# blinking_circuit_training.net
KiCad netlist of a schematic drawn in EAGLE
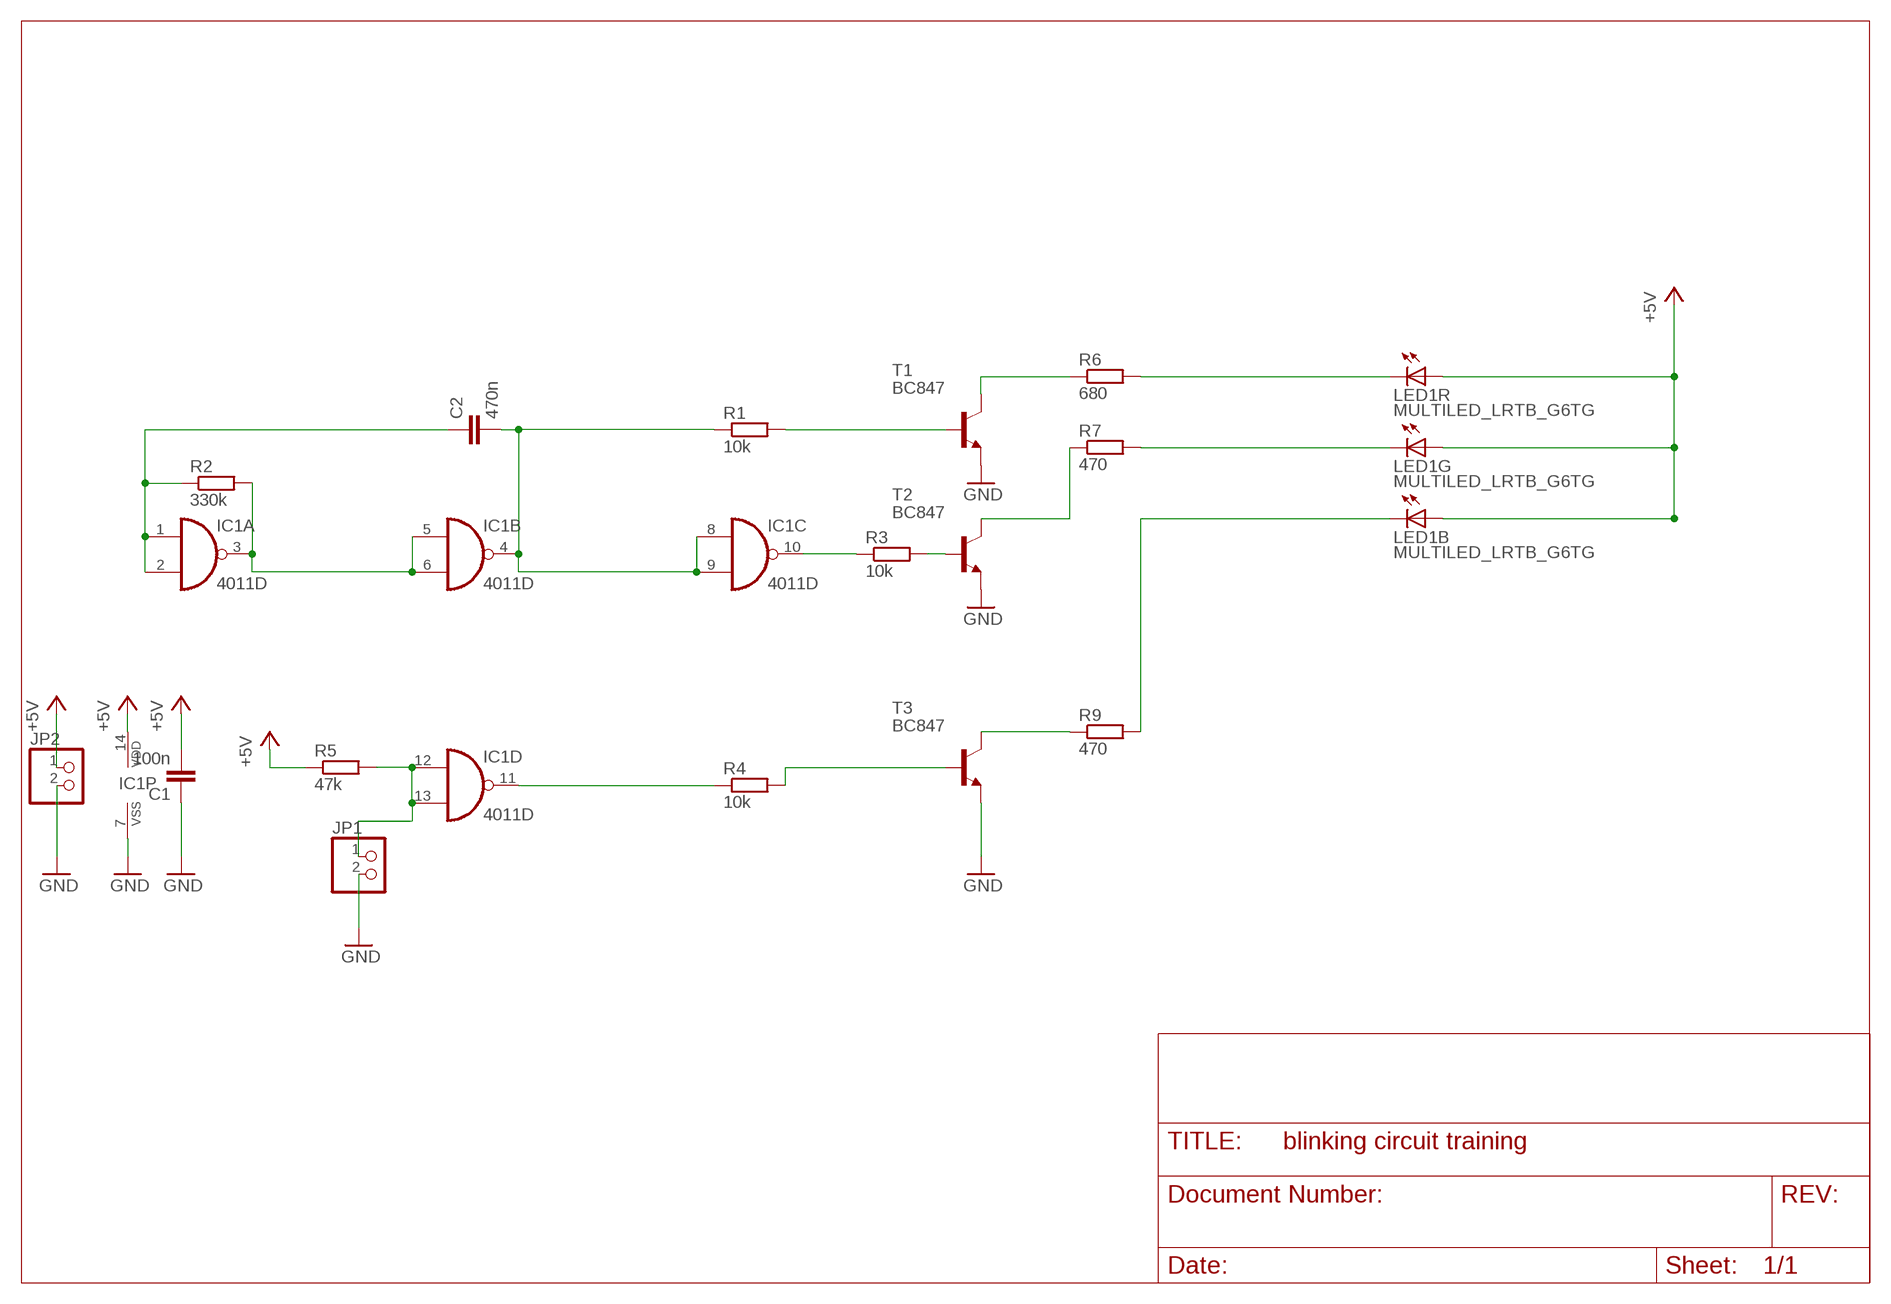
[diagram p0: schematic, sheet 1]

(export (version "E")
  (design (tool "Eeschema 10.0.6"))
  (components
    (comp (ref "C1")
      (value "100n")
      (footprint "eagle-import:C0603")
      (libsource (lib "eagle-import") (part "C-EUC0603"))
    )
    (comp (ref "C2")
      (value "470n")
      (footprint "eagle-import:C0603")
      (libsource (lib "eagle-import") (part "C-EUC0603"))
    )
    (comp (ref "IC1")
      (value "4011D")
      (footprint "eagle-import:SO14")
      (libsource (lib "eagle-import") (part "4011D"))
    )
    (comp (ref "JP1")
      (value "PINHD-1X2")
      (footprint "eagle-import:1X02")
      (libsource (lib "eagle-import") (part "PINHD-1X2"))
    )
    (comp (ref "JP2")
      (value "PINHD-1X2")
      (footprint "eagle-import:1X02")
      (libsource (lib "eagle-import") (part "PINHD-1X2"))
    )
    (comp (ref "LED1")
      (value "MULTILED_LRTB_G6TG")
      (footprint "eagle-import:P-LCC-6_TOPLED")
      (libsource (lib "eagle-import") (part "MULTILED_LRTB_G6TG"))
    )
    (comp (ref "R1")
      (value "10k")
      (footprint "eagle-import:M1206")
      (libsource (lib "eagle-import") (part "R-EU_M1206"))
    )
    (comp (ref "R2")
      (value "330k")
      (footprint "eagle-import:M1206")
      (libsource (lib "eagle-import") (part "R-EU_M1206"))
    )
    (comp (ref "R3")
      (value "10k")
      (footprint "eagle-import:M1206")
      (libsource (lib "eagle-import") (part "R-EU_M1206"))
    )
    (comp (ref "R4")
      (value "10k")
      (footprint "eagle-import:M1206")
      (libsource (lib "eagle-import") (part "R-EU_M1206"))
    )
    (comp (ref "R5")
      (value "47k")
      (footprint "eagle-import:M1206")
      (libsource (lib "eagle-import") (part "R-EU_M1206"))
    )
    (comp (ref "R6")
      (value "680")
      (footprint "eagle-import:M1206")
      (libsource (lib "eagle-import") (part "R-EU_M1206"))
    )
    (comp (ref "R7")
      (value "470")
      (footprint "eagle-import:M1206")
      (libsource (lib "eagle-import") (part "R-EU_M1206"))
    )
    (comp (ref "R9")
      (value "470")
      (footprint "eagle-import:M1206")
      (libsource (lib "eagle-import") (part "R-EU_M1206"))
    )
    (comp (ref "T1")
      (value "BC847")
      (footprint "eagle-import:SOT23")
      (libsource (lib "eagle-import") (part "BC847"))
    )
    (comp (ref "T2")
      (value "BC847")
      (footprint "eagle-import:SOT23")
      (libsource (lib "eagle-import") (part "BC847"))
    )
    (comp (ref "T3")
      (value "BC847")
      (footprint "eagle-import:SOT23")
      (libsource (lib "eagle-import") (part "BC847"))
    )
  )
  (nets
    (net (code "1") (name "+5V") (class "Default")
      (node (ref "C1") (pin "2") (pinfunction "2_2") (pintype "passive"))
      (node (ref "IC1") (pin "14") (pinfunction "VDD_14") (pintype "power_in"))
      (node (ref "JP2") (pin "1") (pinfunction "1_1") (pintype "passive"))
      (node (ref "LED1") (pin "A1") (pinfunction "A_A1") (pintype "passive"))
      (node (ref "LED1") (pin "A2") (pinfunction "A_A2") (pintype "passive"))
      (node (ref "LED1") (pin "A3") (pinfunction "A_A3") (pintype "passive"))
      (node (ref "R5") (pin "1") (pinfunction "1_1") (pintype "passive"))
    )
    (net (code "2") (name "GND") (class "Default")
      (node (ref "C1") (pin "1") (pinfunction "1_1") (pintype "passive"))
      (node (ref "IC1") (pin "7") (pinfunction "VSS_7") (pintype "power_in"))
      (node (ref "JP1") (pin "2") (pinfunction "2_2") (pintype "passive"))
      (node (ref "JP2") (pin "2") (pinfunction "2_2") (pintype "passive"))
      (node (ref "T1") (pin "2") (pinfunction "E_2") (pintype "passive"))
      (node (ref "T2") (pin "2") (pinfunction "E_2") (pintype "passive"))
      (node (ref "T3") (pin "2") (pinfunction "E_2") (pintype "passive"))
    )
    (net (code "3") (name "Net-(IC1A-I0)") (class "Default")
      (node (ref "C2") (pin "1") (pinfunction "1_1") (pintype "passive"))
      (node (ref "IC1") (pin "1") (pinfunction "I0_1") (pintype "input"))
      (node (ref "IC1") (pin "2") (pinfunction "I1_2") (pintype "input"))
      (node (ref "R2") (pin "1") (pinfunction "1_1") (pintype "passive"))
    )
    (net (code "4") (name "Net-(IC1A-O)") (class "Default")
      (node (ref "IC1") (pin "3") (pinfunction "O_3") (pintype "output"))
      (node (ref "IC1") (pin "5") (pinfunction "I0_5") (pintype "input"))
      (node (ref "IC1") (pin "6") (pinfunction "I1_6") (pintype "input"))
      (node (ref "R2") (pin "2") (pinfunction "2_2") (pintype "passive"))
    )
    (net (code "5") (name "Net-(IC1B-O)") (class "Default")
      (node (ref "C2") (pin "2") (pinfunction "2_2") (pintype "passive"))
      (node (ref "IC1") (pin "4") (pinfunction "O_4") (pintype "output"))
      (node (ref "IC1") (pin "8") (pinfunction "I0_8") (pintype "input"))
      (node (ref "IC1") (pin "9") (pinfunction "I1_9") (pintype "input"))
      (node (ref "R1") (pin "1") (pinfunction "1_1") (pintype "passive"))
    )
    (net (code "6") (name "Net-(IC1C-O)") (class "Default")
      (node (ref "IC1") (pin "10") (pinfunction "O_10") (pintype "output"))
      (node (ref "R3") (pin "1") (pinfunction "1_1") (pintype "passive"))
    )
    (net (code "7") (name "Net-(IC1D-I0)") (class "Default")
      (node (ref "IC1") (pin "12") (pinfunction "I0_12") (pintype "input"))
      (node (ref "IC1") (pin "13") (pinfunction "I1_13") (pintype "input"))
      (node (ref "JP1") (pin "1") (pinfunction "1_1") (pintype "passive"))
      (node (ref "R5") (pin "2") (pinfunction "2_2") (pintype "passive"))
    )
    (net (code "8") (name "Net-(IC1D-O)") (class "Default")
      (node (ref "IC1") (pin "11") (pinfunction "O_11") (pintype "output"))
      (node (ref "R4") (pin "1") (pinfunction "1_1") (pintype "passive"))
    )
    (net (code "9") (name "Net-(LED1A-C)") (class "Default")
      (node (ref "LED1") (pin "C3") (pinfunction "C_C3") (pintype "passive"))
      (node (ref "R9") (pin "2") (pinfunction "2_2") (pintype "passive"))
    )
    (net (code "10") (name "Net-(LED1B-C)") (class "Default")
      (node (ref "LED1") (pin "C2") (pinfunction "C_C2") (pintype "passive"))
      (node (ref "R7") (pin "2") (pinfunction "2_2") (pintype "passive"))
    )
    (net (code "11") (name "Net-(LED1C-C)") (class "Default")
      (node (ref "LED1") (pin "C1") (pinfunction "C_C1") (pintype "passive"))
      (node (ref "R6") (pin "2") (pinfunction "2_2") (pintype "passive"))
    )
    (net (code "12") (name "Net-(T1-B)") (class "Default")
      (node (ref "R1") (pin "2") (pinfunction "2_2") (pintype "passive"))
      (node (ref "T1") (pin "1") (pinfunction "B_1") (pintype "passive"))
    )
    (net (code "13") (name "Net-(T1-C)") (class "Default")
      (node (ref "R6") (pin "1") (pinfunction "1_1") (pintype "passive"))
      (node (ref "T1") (pin "3") (pinfunction "C_3") (pintype "passive"))
    )
    (net (code "14") (name "Net-(T2-B)") (class "Default")
      (node (ref "R3") (pin "2") (pinfunction "2_2") (pintype "passive"))
      (node (ref "T2") (pin "1") (pinfunction "B_1") (pintype "passive"))
    )
    (net (code "15") (name "Net-(T2-C)") (class "Default")
      (node (ref "R7") (pin "1") (pinfunction "1_1") (pintype "passive"))
      (node (ref "T2") (pin "3") (pinfunction "C_3") (pintype "passive"))
    )
    (net (code "16") (name "Net-(T3-B)") (class "Default")
      (node (ref "R4") (pin "2") (pinfunction "2_2") (pintype "passive"))
      (node (ref "T3") (pin "1") (pinfunction "B_1") (pintype "passive"))
    )
    (net (code "17") (name "Net-(T3-C)") (class "Default")
      (node (ref "R9") (pin "1") (pinfunction "1_1") (pintype "passive"))
      (node (ref "T3") (pin "3") (pinfunction "C_3") (pintype "passive"))
    )
  )
)
